# LED-Lamp-pth-v3.net
KiCad netlist of a schematic drawn in EAGLE
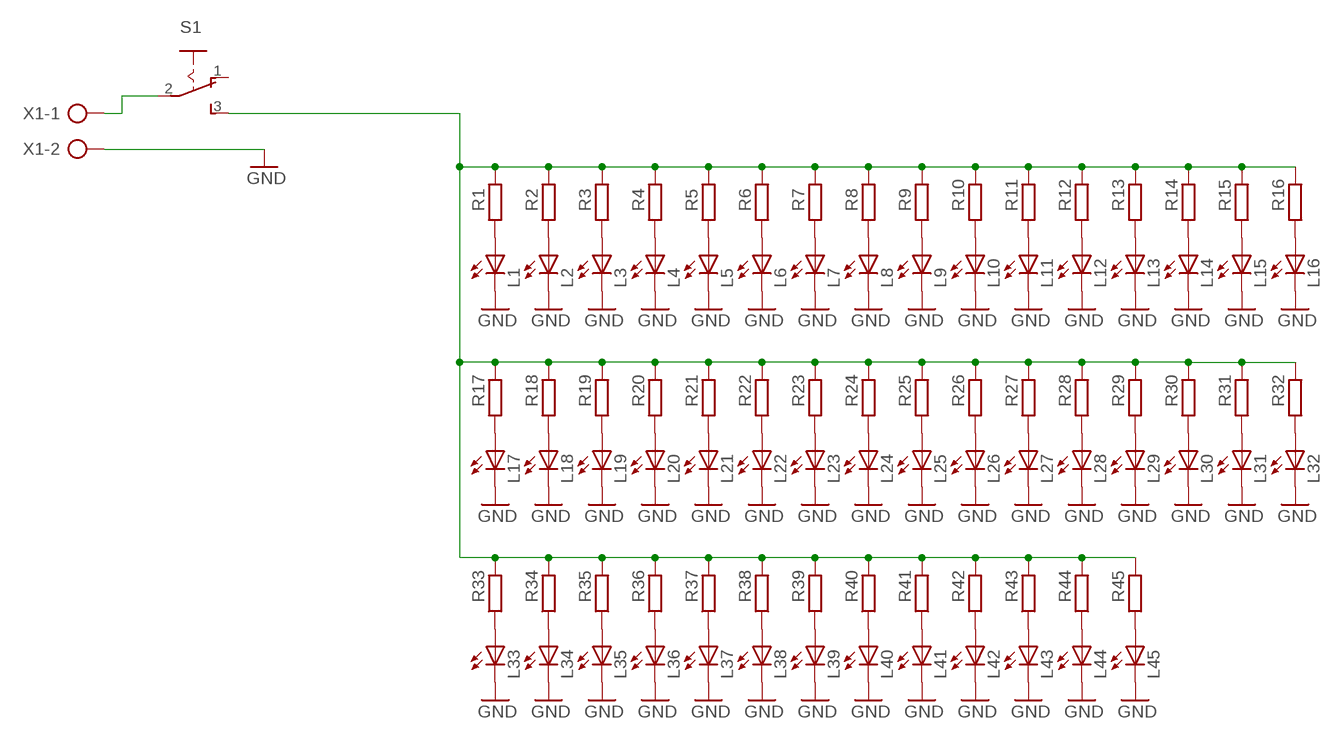
[diagram p0: schematic, sheet 1]

(export (version "E")
  (design (tool "Eeschema 10.0.6"))
  (components
    (comp (ref "L1")
      (value "LEDCHIP-LED0805")
      (footprint "eagle-import:CHIP-LED0805")
      (libsource (lib "eagle-import") (part "LEDCHIP-LED0805"))
    )
    (comp (ref "L2")
      (value "LEDCHIP-LED0805")
      (footprint "eagle-import:CHIP-LED0805")
      (libsource (lib "eagle-import") (part "LEDCHIP-LED0805"))
    )
    (comp (ref "L3")
      (value "LEDCHIP-LED0805")
      (footprint "eagle-import:CHIP-LED0805")
      (libsource (lib "eagle-import") (part "LEDCHIP-LED0805"))
    )
    (comp (ref "L4")
      (value "LEDCHIP-LED0805")
      (footprint "eagle-import:CHIP-LED0805")
      (libsource (lib "eagle-import") (part "LEDCHIP-LED0805"))
    )
    (comp (ref "L5")
      (value "LEDCHIP-LED0805")
      (footprint "eagle-import:CHIP-LED0805")
      (libsource (lib "eagle-import") (part "LEDCHIP-LED0805"))
    )
    (comp (ref "L6")
      (value "LEDCHIP-LED0805")
      (footprint "eagle-import:CHIP-LED0805")
      (libsource (lib "eagle-import") (part "LEDCHIP-LED0805"))
    )
    (comp (ref "L7")
      (value "LEDCHIP-LED0805")
      (footprint "eagle-import:CHIP-LED0805")
      (libsource (lib "eagle-import") (part "LEDCHIP-LED0805"))
    )
    (comp (ref "L8")
      (value "LEDCHIP-LED0805")
      (footprint "eagle-import:CHIP-LED0805")
      (libsource (lib "eagle-import") (part "LEDCHIP-LED0805"))
    )
    (comp (ref "L9")
      (value "LEDCHIP-LED0805")
      (footprint "eagle-import:CHIP-LED0805")
      (libsource (lib "eagle-import") (part "LEDCHIP-LED0805"))
    )
    (comp (ref "L10")
      (value "LEDCHIP-LED0805")
      (footprint "eagle-import:CHIP-LED0805")
      (libsource (lib "eagle-import") (part "LEDCHIP-LED0805"))
    )
    (comp (ref "L11")
      (value "LEDCHIP-LED0805")
      (footprint "eagle-import:CHIP-LED0805")
      (libsource (lib "eagle-import") (part "LEDCHIP-LED0805"))
    )
    (comp (ref "L12")
      (value "LEDCHIP-LED0805")
      (footprint "eagle-import:CHIP-LED0805")
      (libsource (lib "eagle-import") (part "LEDCHIP-LED0805"))
    )
    (comp (ref "L13")
      (value "LEDCHIP-LED0805")
      (footprint "eagle-import:CHIP-LED0805")
      (libsource (lib "eagle-import") (part "LEDCHIP-LED0805"))
    )
    (comp (ref "L14")
      (value "LEDCHIP-LED0805")
      (footprint "eagle-import:CHIP-LED0805")
      (libsource (lib "eagle-import") (part "LEDCHIP-LED0805"))
    )
    (comp (ref "L15")
      (value "LEDCHIP-LED0805")
      (footprint "eagle-import:CHIP-LED0805")
      (libsource (lib "eagle-import") (part "LEDCHIP-LED0805"))
    )
    (comp (ref "L16")
      (value "LEDCHIP-LED0805")
      (footprint "eagle-import:CHIP-LED0805")
      (libsource (lib "eagle-import") (part "LEDCHIP-LED0805"))
    )
    (comp (ref "L17")
      (value "LEDCHIP-LED0805")
      (footprint "eagle-import:CHIP-LED0805")
      (libsource (lib "eagle-import") (part "LEDCHIP-LED0805"))
    )
    (comp (ref "L18")
      (value "LEDCHIP-LED0805")
      (footprint "eagle-import:CHIP-LED0805")
      (libsource (lib "eagle-import") (part "LEDCHIP-LED0805"))
    )
    (comp (ref "L19")
      (value "LEDCHIP-LED0805")
      (footprint "eagle-import:CHIP-LED0805")
      (libsource (lib "eagle-import") (part "LEDCHIP-LED0805"))
    )
    (comp (ref "L20")
      (value "LEDCHIP-LED0805")
      (footprint "eagle-import:CHIP-LED0805")
      (libsource (lib "eagle-import") (part "LEDCHIP-LED0805"))
    )
    (comp (ref "L21")
      (value "LEDCHIP-LED0805")
      (footprint "eagle-import:CHIP-LED0805")
      (libsource (lib "eagle-import") (part "LEDCHIP-LED0805"))
    )
    (comp (ref "L22")
      (value "LEDCHIP-LED0805")
      (footprint "eagle-import:CHIP-LED0805")
      (libsource (lib "eagle-import") (part "LEDCHIP-LED0805"))
    )
    (comp (ref "L23")
      (value "LEDCHIP-LED0805")
      (footprint "eagle-import:CHIP-LED0805")
      (libsource (lib "eagle-import") (part "LEDCHIP-LED0805"))
    )
    (comp (ref "L24")
      (value "LEDCHIP-LED0805")
      (footprint "eagle-import:CHIP-LED0805")
      (libsource (lib "eagle-import") (part "LEDCHIP-LED0805"))
    )
    (comp (ref "L25")
      (value "LEDCHIP-LED0805")
      (footprint "eagle-import:CHIP-LED0805")
      (libsource (lib "eagle-import") (part "LEDCHIP-LED0805"))
    )
    (comp (ref "L26")
      (value "LEDCHIP-LED0805")
      (footprint "eagle-import:CHIP-LED0805")
      (libsource (lib "eagle-import") (part "LEDCHIP-LED0805"))
    )
    (comp (ref "L27")
      (value "LEDCHIP-LED0805")
      (footprint "eagle-import:CHIP-LED0805")
      (libsource (lib "eagle-import") (part "LEDCHIP-LED0805"))
    )
    (comp (ref "L28")
      (value "LEDCHIP-LED0805")
      (footprint "eagle-import:CHIP-LED0805")
      (libsource (lib "eagle-import") (part "LEDCHIP-LED0805"))
    )
    (comp (ref "L29")
      (value "LEDCHIP-LED0805")
      (footprint "eagle-import:CHIP-LED0805")
      (libsource (lib "eagle-import") (part "LEDCHIP-LED0805"))
    )
    (comp (ref "L30")
      (value "LEDCHIP-LED0805")
      (footprint "eagle-import:CHIP-LED0805")
      (libsource (lib "eagle-import") (part "LEDCHIP-LED0805"))
    )
    (comp (ref "L31")
      (value "LEDCHIP-LED0805")
      (footprint "eagle-import:CHIP-LED0805")
      (libsource (lib "eagle-import") (part "LEDCHIP-LED0805"))
    )
    (comp (ref "L32")
      (value "LEDCHIP-LED0805")
      (footprint "eagle-import:CHIP-LED0805")
      (libsource (lib "eagle-import") (part "LEDCHIP-LED0805"))
    )
    (comp (ref "L33")
      (value "LEDCHIP-LED0805")
      (footprint "eagle-import:CHIP-LED0805")
      (libsource (lib "eagle-import") (part "LEDCHIP-LED0805"))
    )
    (comp (ref "L34")
      (value "LEDCHIP-LED0805")
      (footprint "eagle-import:CHIP-LED0805")
      (libsource (lib "eagle-import") (part "LEDCHIP-LED0805"))
    )
    (comp (ref "L35")
      (value "LEDCHIP-LED0805")
      (footprint "eagle-import:CHIP-LED0805")
      (libsource (lib "eagle-import") (part "LEDCHIP-LED0805"))
    )
    (comp (ref "L36")
      (value "LEDCHIP-LED0805")
      (footprint "eagle-import:CHIP-LED0805")
      (libsource (lib "eagle-import") (part "LEDCHIP-LED0805"))
    )
    (comp (ref "L37")
      (value "LEDCHIP-LED0805")
      (footprint "eagle-import:CHIP-LED0805")
      (libsource (lib "eagle-import") (part "LEDCHIP-LED0805"))
    )
    (comp (ref "L38")
      (value "LEDCHIP-LED0805")
      (footprint "eagle-import:CHIP-LED0805")
      (libsource (lib "eagle-import") (part "LEDCHIP-LED0805"))
    )
    (comp (ref "L39")
      (value "LEDCHIP-LED0805")
      (footprint "eagle-import:CHIP-LED0805")
      (libsource (lib "eagle-import") (part "LEDCHIP-LED0805"))
    )
    (comp (ref "L40")
      (value "LEDCHIP-LED0805")
      (footprint "eagle-import:CHIP-LED0805")
      (libsource (lib "eagle-import") (part "LEDCHIP-LED0805"))
    )
    (comp (ref "L41")
      (value "LEDCHIP-LED0805")
      (footprint "eagle-import:CHIP-LED0805")
      (libsource (lib "eagle-import") (part "LEDCHIP-LED0805"))
    )
    (comp (ref "L42")
      (value "LEDCHIP-LED0805")
      (footprint "eagle-import:CHIP-LED0805")
      (libsource (lib "eagle-import") (part "LEDCHIP-LED0805"))
    )
    (comp (ref "L43")
      (value "LEDCHIP-LED0805")
      (footprint "eagle-import:CHIP-LED0805")
      (libsource (lib "eagle-import") (part "LEDCHIP-LED0805"))
    )
    (comp (ref "L44")
      (value "LEDCHIP-LED0805")
      (footprint "eagle-import:CHIP-LED0805")
      (libsource (lib "eagle-import") (part "LEDCHIP-LED0805"))
    )
    (comp (ref "L45")
      (value "LEDCHIP-LED0805")
      (footprint "eagle-import:CHIP-LED0805")
      (libsource (lib "eagle-import") (part "LEDCHIP-LED0805"))
    )
    (comp (ref "R1")
      (value "R-EU_0207/7")
      (footprint "eagle-import:0207_7")
      (libsource (lib "eagle-import") (part "R-EU_0207/7"))
    )
    (comp (ref "R2")
      (value "R-EU_0207/7")
      (footprint "eagle-import:0207_7")
      (libsource (lib "eagle-import") (part "R-EU_0207/7"))
    )
    (comp (ref "R3")
      (value "R-EU_0207/7")
      (footprint "eagle-import:0207_7")
      (libsource (lib "eagle-import") (part "R-EU_0207/7"))
    )
    (comp (ref "R4")
      (value "R-EU_0207/7")
      (footprint "eagle-import:0207_7")
      (libsource (lib "eagle-import") (part "R-EU_0207/7"))
    )
    (comp (ref "R5")
      (value "R-EU_0207/7")
      (footprint "eagle-import:0207_7")
      (libsource (lib "eagle-import") (part "R-EU_0207/7"))
    )
    (comp (ref "R6")
      (value "R-EU_0207/7")
      (footprint "eagle-import:0207_7")
      (libsource (lib "eagle-import") (part "R-EU_0207/7"))
    )
    (comp (ref "R7")
      (value "R-EU_0207/7")
      (footprint "eagle-import:0207_7")
      (libsource (lib "eagle-import") (part "R-EU_0207/7"))
    )
    (comp (ref "R8")
      (value "R-EU_0207/7")
      (footprint "eagle-import:0207_7")
      (libsource (lib "eagle-import") (part "R-EU_0207/7"))
    )
    (comp (ref "R9")
      (value "R-EU_0207/7")
      (footprint "eagle-import:0207_7")
      (libsource (lib "eagle-import") (part "R-EU_0207/7"))
    )
    (comp (ref "R10")
      (value "R-EU_0207/7")
      (footprint "eagle-import:0207_7")
      (libsource (lib "eagle-import") (part "R-EU_0207/7"))
    )
    (comp (ref "R11")
      (value "R-EU_0207/7")
      (footprint "eagle-import:0207_7")
      (libsource (lib "eagle-import") (part "R-EU_0207/7"))
    )
    (comp (ref "R12")
      (value "R-EU_0207/7")
      (footprint "eagle-import:0207_7")
      (libsource (lib "eagle-import") (part "R-EU_0207/7"))
    )
    (comp (ref "R13")
      (value "R-EU_0207/7")
      (footprint "eagle-import:0207_7")
      (libsource (lib "eagle-import") (part "R-EU_0207/7"))
    )
    (comp (ref "R14")
      (value "R-EU_0207/7")
      (footprint "eagle-import:0207_7")
      (libsource (lib "eagle-import") (part "R-EU_0207/7"))
    )
    (comp (ref "R15")
      (value "R-EU_0207/7")
      (footprint "eagle-import:0207_7")
      (libsource (lib "eagle-import") (part "R-EU_0207/7"))
    )
    (comp (ref "R16")
      (value "R-EU_0207/7")
      (footprint "eagle-import:0207_7")
      (libsource (lib "eagle-import") (part "R-EU_0207/7"))
    )
    (comp (ref "R17")
      (value "R-EU_0207/7")
      (footprint "eagle-import:0207_7")
      (libsource (lib "eagle-import") (part "R-EU_0207/7"))
    )
    (comp (ref "R18")
      (value "R-EU_0207/7")
      (footprint "eagle-import:0207_7")
      (libsource (lib "eagle-import") (part "R-EU_0207/7"))
    )
    (comp (ref "R19")
      (value "R-EU_0207/7")
      (footprint "eagle-import:0207_7")
      (libsource (lib "eagle-import") (part "R-EU_0207/7"))
    )
    (comp (ref "R20")
      (value "R-EU_0207/7")
      (footprint "eagle-import:0207_7")
      (libsource (lib "eagle-import") (part "R-EU_0207/7"))
    )
    (comp (ref "R21")
      (value "R-EU_0207/7")
      (footprint "eagle-import:0207_7")
      (libsource (lib "eagle-import") (part "R-EU_0207/7"))
    )
    (comp (ref "R22")
      (value "R-EU_0207/7")
      (footprint "eagle-import:0207_7")
      (libsource (lib "eagle-import") (part "R-EU_0207/7"))
    )
    (comp (ref "R23")
      (value "R-EU_0207/7")
      (footprint "eagle-import:0207_7")
      (libsource (lib "eagle-import") (part "R-EU_0207/7"))
    )
    (comp (ref "R24")
      (value "R-EU_0207/7")
      (footprint "eagle-import:0207_7")
      (libsource (lib "eagle-import") (part "R-EU_0207/7"))
    )
    (comp (ref "R25")
      (value "R-EU_0207/7")
      (footprint "eagle-import:0207_7")
      (libsource (lib "eagle-import") (part "R-EU_0207/7"))
    )
    (comp (ref "R26")
      (value "R-EU_0207/7")
      (footprint "eagle-import:0207_7")
      (libsource (lib "eagle-import") (part "R-EU_0207/7"))
    )
    (comp (ref "R27")
      (value "R-EU_0207/7")
      (footprint "eagle-import:0207_7")
      (libsource (lib "eagle-import") (part "R-EU_0207/7"))
    )
    (comp (ref "R28")
      (value "R-EU_0207/7")
      (footprint "eagle-import:0207_7")
      (libsource (lib "eagle-import") (part "R-EU_0207/7"))
    )
    (comp (ref "R29")
      (value "R-EU_0207/7")
      (footprint "eagle-import:0207_7")
      (libsource (lib "eagle-import") (part "R-EU_0207/7"))
    )
    (comp (ref "R30")
      (value "R-EU_0207/7")
      (footprint "eagle-import:0207_7")
      (libsource (lib "eagle-import") (part "R-EU_0207/7"))
    )
    (comp (ref "R31")
      (value "R-EU_0207/7")
      (footprint "eagle-import:0207_7")
      (libsource (lib "eagle-import") (part "R-EU_0207/7"))
    )
    (comp (ref "R32")
      (value "R-EU_0207/7")
      (footprint "eagle-import:0207_7")
      (libsource (lib "eagle-import") (part "R-EU_0207/7"))
    )
    (comp (ref "R33")
      (value "R-EU_0207/7")
      (footprint "eagle-import:0207_7")
      (libsource (lib "eagle-import") (part "R-EU_0207/7"))
    )
    (comp (ref "R34")
      (value "R-EU_0207/7")
      (footprint "eagle-import:0207_7")
      (libsource (lib "eagle-import") (part "R-EU_0207/7"))
    )
    (comp (ref "R35")
      (value "R-EU_0207/7")
      (footprint "eagle-import:0207_7")
      (libsource (lib "eagle-import") (part "R-EU_0207/7"))
    )
    (comp (ref "R36")
      (value "R-EU_0207/7")
      (footprint "eagle-import:0207_7")
      (libsource (lib "eagle-import") (part "R-EU_0207/7"))
    )
    (comp (ref "R37")
      (value "R-EU_0207/7")
      (footprint "eagle-import:0207_7")
      (libsource (lib "eagle-import") (part "R-EU_0207/7"))
    )
    (comp (ref "R38")
      (value "R-EU_0207/7")
      (footprint "eagle-import:0207_7")
      (libsource (lib "eagle-import") (part "R-EU_0207/7"))
    )
    (comp (ref "R39")
      (value "R-EU_0207/7")
      (footprint "eagle-import:0207_7")
      (libsource (lib "eagle-import") (part "R-EU_0207/7"))
    )
    (comp (ref "R40")
      (value "R-EU_0207/7")
      (footprint "eagle-import:0207_7")
      (libsource (lib "eagle-import") (part "R-EU_0207/7"))
    )
    (comp (ref "R41")
      (value "R-EU_0207/7")
      (footprint "eagle-import:0207_7")
      (libsource (lib "eagle-import") (part "R-EU_0207/7"))
    )
    (comp (ref "R42")
      (value "R-EU_0207/7")
      (footprint "eagle-import:0207_7")
      (libsource (lib "eagle-import") (part "R-EU_0207/7"))
    )
    (comp (ref "R43")
      (value "R-EU_0207/7")
      (footprint "eagle-import:0207_7")
      (libsource (lib "eagle-import") (part "R-EU_0207/7"))
    )
    (comp (ref "R44")
      (value "R-EU_0207/7")
      (footprint "eagle-import:0207_7")
      (libsource (lib "eagle-import") (part "R-EU_0207/7"))
    )
    (comp (ref "R45")
      (value "R-EU_0207/7")
      (footprint "eagle-import:0207_7")
      (libsource (lib "eagle-import") (part "R-EU_0207/7"))
    )
    (comp (ref "S1")
      (value "255SB")
      (footprint "eagle-import:255SB")
      (libsource (lib "eagle-import") (part "255SB"))
    )
    (comp (ref "X1")
      (value "AK300/2")
      (footprint "eagle-import:AK300_2")
      (libsource (lib "eagle-import") (part "AK300/2"))
    )
  )
  (nets
    (net (code "1") (name "GND") (class "Default")
      (node (ref "L1") (pin "C") (pinfunction "C_C") (pintype "passive"))
      (node (ref "L10") (pin "C") (pinfunction "C_C") (pintype "passive"))
      (node (ref "L11") (pin "C") (pinfunction "C_C") (pintype "passive"))
      (node (ref "L12") (pin "C") (pinfunction "C_C") (pintype "passive"))
      (node (ref "L13") (pin "C") (pinfunction "C_C") (pintype "passive"))
      (node (ref "L14") (pin "C") (pinfunction "C_C") (pintype "passive"))
      (node (ref "L15") (pin "C") (pinfunction "C_C") (pintype "passive"))
      (node (ref "L16") (pin "C") (pinfunction "C_C") (pintype "passive"))
      (node (ref "L17") (pin "C") (pinfunction "C_C") (pintype "passive"))
      (node (ref "L18") (pin "C") (pinfunction "C_C") (pintype "passive"))
      (node (ref "L19") (pin "C") (pinfunction "C_C") (pintype "passive"))
      (node (ref "L2") (pin "C") (pinfunction "C_C") (pintype "passive"))
      (node (ref "L20") (pin "C") (pinfunction "C_C") (pintype "passive"))
      (node (ref "L21") (pin "C") (pinfunction "C_C") (pintype "passive"))
      (node (ref "L22") (pin "C") (pinfunction "C_C") (pintype "passive"))
      (node (ref "L23") (pin "C") (pinfunction "C_C") (pintype "passive"))
      (node (ref "L24") (pin "C") (pinfunction "C_C") (pintype "passive"))
      (node (ref "L25") (pin "C") (pinfunction "C_C") (pintype "passive"))
      (node (ref "L26") (pin "C") (pinfunction "C_C") (pintype "passive"))
      (node (ref "L27") (pin "C") (pinfunction "C_C") (pintype "passive"))
      (node (ref "L28") (pin "C") (pinfunction "C_C") (pintype "passive"))
      (node (ref "L29") (pin "C") (pinfunction "C_C") (pintype "passive"))
      (node (ref "L3") (pin "C") (pinfunction "C_C") (pintype "passive"))
      (node (ref "L30") (pin "C") (pinfunction "C_C") (pintype "passive"))
      (node (ref "L31") (pin "C") (pinfunction "C_C") (pintype "passive"))
      (node (ref "L32") (pin "C") (pinfunction "C_C") (pintype "passive"))
      (node (ref "L33") (pin "C") (pinfunction "C_C") (pintype "passive"))
      (node (ref "L34") (pin "C") (pinfunction "C_C") (pintype "passive"))
      (node (ref "L35") (pin "C") (pinfunction "C_C") (pintype "passive"))
      (node (ref "L36") (pin "C") (pinfunction "C_C") (pintype "passive"))
      (node (ref "L37") (pin "C") (pinfunction "C_C") (pintype "passive"))
      (node (ref "L38") (pin "C") (pinfunction "C_C") (pintype "passive"))
      (node (ref "L39") (pin "C") (pinfunction "C_C") (pintype "passive"))
      (node (ref "L4") (pin "C") (pinfunction "C_C") (pintype "passive"))
      (node (ref "L40") (pin "C") (pinfunction "C_C") (pintype "passive"))
      (node (ref "L41") (pin "C") (pinfunction "C_C") (pintype "passive"))
      (node (ref "L42") (pin "C") (pinfunction "C_C") (pintype "passive"))
      (node (ref "L43") (pin "C") (pinfunction "C_C") (pintype "passive"))
      (node (ref "L44") (pin "C") (pinfunction "C_C") (pintype "passive"))
      (node (ref "L45") (pin "C") (pinfunction "C_C") (pintype "passive"))
      (node (ref "L5") (pin "C") (pinfunction "C_C") (pintype "passive"))
      (node (ref "L6") (pin "C") (pinfunction "C_C") (pintype "passive"))
      (node (ref "L7") (pin "C") (pinfunction "C_C") (pintype "passive"))
      (node (ref "L8") (pin "C") (pinfunction "C_C") (pintype "passive"))
      (node (ref "L9") (pin "C") (pinfunction "C_C") (pintype "passive"))
      (node (ref "X1") (pin "2") (pinfunction "KL_2") (pintype "passive"))
    )
    (net (code "2") (name "Net-(L1-PadA)") (class "Default")
      (node (ref "L1") (pin "A") (pinfunction "A_A") (pintype "passive"))
      (node (ref "R1") (pin "1") (pinfunction "1_1") (pintype "passive"))
    )
    (net (code "3") (name "Net-(L2-PadA)") (class "Default")
      (node (ref "L2") (pin "A") (pinfunction "A_A") (pintype "passive"))
      (node (ref "R2") (pin "1") (pinfunction "1_1") (pintype "passive"))
    )
    (net (code "4") (name "Net-(L3-PadA)") (class "Default")
      (node (ref "L3") (pin "A") (pinfunction "A_A") (pintype "passive"))
      (node (ref "R3") (pin "1") (pinfunction "1_1") (pintype "passive"))
    )
    (net (code "5") (name "Net-(L4-PadA)") (class "Default")
      (node (ref "L4") (pin "A") (pinfunction "A_A") (pintype "passive"))
      (node (ref "R4") (pin "1") (pinfunction "1_1") (pintype "passive"))
    )
    (net (code "6") (name "Net-(L5-PadA)") (class "Default")
      (node (ref "L5") (pin "A") (pinfunction "A_A") (pintype "passive"))
      (node (ref "R5") (pin "1") (pinfunction "1_1") (pintype "passive"))
    )
    (net (code "7") (name "Net-(L6-PadA)") (class "Default")
      (node (ref "L6") (pin "A") (pinfunction "A_A") (pintype "passive"))
      (node (ref "R6") (pin "1") (pinfunction "1_1") (pintype "passive"))
    )
    (net (code "8") (name "Net-(L7-PadA)") (class "Default")
      (node (ref "L7") (pin "A") (pinfunction "A_A") (pintype "passive"))
      (node (ref "R7") (pin "1") (pinfunction "1_1") (pintype "passive"))
    )
    (net (code "9") (name "Net-(L8-PadA)") (class "Default")
      (node (ref "L8") (pin "A") (pinfunction "A_A") (pintype "passive"))
      (node (ref "R8") (pin "1") (pinfunction "1_1") (pintype "passive"))
    )
    (net (code "10") (name "Net-(L9-PadA)") (class "Default")
      (node (ref "L9") (pin "A") (pinfunction "A_A") (pintype "passive"))
      (node (ref "R9") (pin "1") (pinfunction "1_1") (pintype "passive"))
    )
    (net (code "11") (name "Net-(L10-PadA)") (class "Default")
      (node (ref "L10") (pin "A") (pinfunction "A_A") (pintype "passive"))
      (node (ref "R10") (pin "1") (pinfunction "1_1") (pintype "passive"))
    )
    (net (code "12") (name "Net-(L11-PadA)") (class "Default")
      (node (ref "L11") (pin "A") (pinfunction "A_A") (pintype "passive"))
      (node (ref "R11") (pin "1") (pinfunction "1_1") (pintype "passive"))
    )
    (net (code "13") (name "Net-(L12-PadA)") (class "Default")
      (node (ref "L12") (pin "A") (pinfunction "A_A") (pintype "passive"))
      (node (ref "R12") (pin "1") (pinfunction "1_1") (pintype "passive"))
    )
    (net (code "14") (name "Net-(L13-PadA)") (class "Default")
      (node (ref "L13") (pin "A") (pinfunction "A_A") (pintype "passive"))
      (node (ref "R13") (pin "1") (pinfunction "1_1") (pintype "passive"))
    )
    (net (code "15") (name "Net-(L14-PadA)") (class "Default")
      (node (ref "L14") (pin "A") (pinfunction "A_A") (pintype "passive"))
      (node (ref "R14") (pin "1") (pinfunction "1_1") (pintype "passive"))
    )
    (net (code "16") (name "Net-(L15-PadA)") (class "Default")
      (node (ref "L15") (pin "A") (pinfunction "A_A") (pintype "passive"))
      (node (ref "R15") (pin "1") (pinfunction "1_1") (pintype "passive"))
    )
    (net (code "17") (name "Net-(L16-PadA)") (class "Default")
      (node (ref "L16") (pin "A") (pinfunction "A_A") (pintype "passive"))
      (node (ref "R16") (pin "1") (pinfunction "1_1") (pintype "passive"))
    )
    (net (code "18") (name "Net-(L17-PadA)") (class "Default")
      (node (ref "L17") (pin "A") (pinfunction "A_A") (pintype "passive"))
      (node (ref "R17") (pin "1") (pinfunction "1_1") (pintype "passive"))
    )
    (net (code "19") (name "Net-(L18-PadA)") (class "Default")
      (node (ref "L18") (pin "A") (pinfunction "A_A") (pintype "passive"))
      (node (ref "R18") (pin "1") (pinfunction "1_1") (pintype "passive"))
    )
    (net (code "20") (name "Net-(L19-PadA)") (class "Default")
      (node (ref "L19") (pin "A") (pinfunction "A_A") (pintype "passive"))
      (node (ref "R19") (pin "1") (pinfunction "1_1") (pintype "passive"))
    )
    (net (code "21") (name "Net-(L20-PadA)") (class "Default")
      (node (ref "L20") (pin "A") (pinfunction "A_A") (pintype "passive"))
      (node (ref "R20") (pin "1") (pinfunction "1_1") (pintype "passive"))
    )
    (net (code "22") (name "Net-(L21-PadA)") (class "Default")
      (node (ref "L21") (pin "A") (pinfunction "A_A") (pintype "passive"))
      (node (ref "R21") (pin "1") (pinfunction "1_1") (pintype "passive"))
    )
    (net (code "23") (name "Net-(L22-PadA)") (class "Default")
      (node (ref "L22") (pin "A") (pinfunction "A_A") (pintype "passive"))
      (node (ref "R22") (pin "1") (pinfunction "1_1") (pintype "passive"))
    )
    (net (code "24") (name "Net-(L23-PadA)") (class "Default")
      (node (ref "L23") (pin "A") (pinfunction "A_A") (pintype "passive"))
      (node (ref "R23") (pin "1") (pinfunction "1_1") (pintype "passive"))
    )
    (net (code "25") (name "Net-(L24-PadA)") (class "Default")
      (node (ref "L24") (pin "A") (pinfunction "A_A") (pintype "passive"))
      (node (ref "R24") (pin "1") (pinfunction "1_1") (pintype "passive"))
    )
    (net (code "26") (name "Net-(L25-PadA)") (class "Default")
      (node (ref "L25") (pin "A") (pinfunction "A_A") (pintype "passive"))
      (node (ref "R25") (pin "1") (pinfunction "1_1") (pintype "passive"))
    )
    (net (code "27") (name "Net-(L26-PadA)") (class "Default")
      (node (ref "L26") (pin "A") (pinfunction "A_A") (pintype "passive"))
      (node (ref "R26") (pin "1") (pinfunction "1_1") (pintype "passive"))
    )
    (net (code "28") (name "Net-(L27-PadA)") (class "Default")
      (node (ref "L27") (pin "A") (pinfunction "A_A") (pintype "passive"))
      (node (ref "R27") (pin "1") (pinfunction "1_1") (pintype "passive"))
    )
    (net (code "29") (name "Net-(L28-PadA)") (class "Default")
      (node (ref "L28") (pin "A") (pinfunction "A_A") (pintype "passive"))
      (node (ref "R28") (pin "1") (pinfunction "1_1") (pintype "passive"))
    )
    (net (code "30") (name "Net-(L29-PadA)") (class "Default")
      (node (ref "L29") (pin "A") (pinfunction "A_A") (pintype "passive"))
      (node (ref "R29") (pin "1") (pinfunction "1_1") (pintype "passive"))
    )
    (net (code "31") (name "Net-(L30-PadA)") (class "Default")
      (node (ref "L30") (pin "A") (pinfunction "A_A") (pintype "passive"))
      (node (ref "R30") (pin "1") (pinfunction "1_1") (pintype "passive"))
    )
    (net (code "32") (name "Net-(L31-PadA)") (class "Default")
      (node (ref "L31") (pin "A") (pinfunction "A_A") (pintype "passive"))
      (node (ref "R31") (pin "1") (pinfunction "1_1") (pintype "passive"))
    )
    (net (code "33") (name "Net-(L32-PadA)") (class "Default")
      (node (ref "L32") (pin "A") (pinfunction "A_A") (pintype "passive"))
      (node (ref "R32") (pin "1") (pinfunction "1_1") (pintype "passive"))
    )
    (net (code "34") (name "Net-(L33-PadA)") (class "Default")
      (node (ref "L33") (pin "A") (pinfunction "A_A") (pintype "passive"))
      (node (ref "R33") (pin "1") (pinfunction "1_1") (pintype "passive"))
    )
    (net (code "35") (name "Net-(L34-PadA)") (class "Default")
      (node (ref "L34") (pin "A") (pinfunction "A_A") (pintype "passive"))
      (node (ref "R34") (pin "1") (pinfunction "1_1") (pintype "passive"))
    )
    (net (code "36") (name "Net-(L35-PadA)") (class "Default")
      (node (ref "L35") (pin "A") (pinfunction "A_A") (pintype "passive"))
      (node (ref "R35") (pin "1") (pinfunction "1_1") (pintype "passive"))
    )
    (net (code "37") (name "Net-(L36-PadA)") (class "Default")
      (node (ref "L36") (pin "A") (pinfunction "A_A") (pintype "passive"))
      (node (ref "R36") (pin "1") (pinfunction "1_1") (pintype "passive"))
    )
    (net (code "38") (name "Net-(L37-PadA)") (class "Default")
      (node (ref "L37") (pin "A") (pinfunction "A_A") (pintype "passive"))
      (node (ref "R37") (pin "1") (pinfunction "1_1") (pintype "passive"))
    )
    (net (code "39") (name "Net-(L38-PadA)") (class "Default")
      (node (ref "L38") (pin "A") (pinfunction "A_A") (pintype "passive"))
      (node (ref "R38") (pin "1") (pinfunction "1_1") (pintype "passive"))
    )
    (net (code "40") (name "Net-(L39-PadA)") (class "Default")
      (node (ref "L39") (pin "A") (pinfunction "A_A") (pintype "passive"))
      (node (ref "R39") (pin "1") (pinfunction "1_1") (pintype "passive"))
    )
    (net (code "41") (name "Net-(L40-PadA)") (class "Default")
      (node (ref "L40") (pin "A") (pinfunction "A_A") (pintype "passive"))
      (node (ref "R40") (pin "1") (pinfunction "1_1") (pintype "passive"))
    )
    (net (code "42") (name "Net-(L41-PadA)") (class "Default")
      (node (ref "L41") (pin "A") (pinfunction "A_A") (pintype "passive"))
      (node (ref "R41") (pin "1") (pinfunction "1_1") (pintype "passive"))
    )
    (net (code "43") (name "Net-(L42-PadA)") (class "Default")
      (node (ref "L42") (pin "A") (pinfunction "A_A") (pintype "passive"))
      (node (ref "R42") (pin "1") (pinfunction "1_1") (pintype "passive"))
    )
    (net (code "44") (name "Net-(L43-PadA)") (class "Default")
      (node (ref "L43") (pin "A") (pinfunction "A_A") (pintype "passive"))
      (node (ref "R43") (pin "1") (pinfunction "1_1") (pintype "passive"))
    )
    (net (code "45") (name "Net-(L44-PadA)") (class "Default")
      (node (ref "L44") (pin "A") (pinfunction "A_A") (pintype "passive"))
      (node (ref "R44") (pin "1") (pinfunction "1_1") (pintype "passive"))
    )
    (net (code "46") (name "Net-(L45-PadA)") (class "Default")
      (node (ref "L45") (pin "A") (pinfunction "A_A") (pintype "passive"))
      (node (ref "R45") (pin "1") (pinfunction "1_1") (pintype "passive"))
    )
    (net (code "47") (name "Net-(S1-P)") (class "Default")
      (node (ref "S1") (pin "2") (pinfunction "P_2") (pintype "passive"))
      (node (ref "X1") (pin "1") (pinfunction "KL_1") (pintype "passive"))
    )
    (net (code "48") (name "Net-(S1-S)") (class "Default")
      (node (ref "R1") (pin "2") (pinfunction "2_2") (pintype "passive"))
      (node (ref "R10") (pin "2") (pinfunction "2_2") (pintype "passive"))
      (node (ref "R11") (pin "2") (pinfunction "2_2") (pintype "passive"))
      (node (ref "R12") (pin "2") (pinfunction "2_2") (pintype "passive"))
      (node (ref "R13") (pin "2") (pinfunction "2_2") (pintype "passive"))
      (node (ref "R14") (pin "2") (pinfunction "2_2") (pintype "passive"))
      (node (ref "R15") (pin "2") (pinfunction "2_2") (pintype "passive"))
      (node (ref "R16") (pin "2") (pinfunction "2_2") (pintype "passive"))
      (node (ref "R17") (pin "2") (pinfunction "2_2") (pintype "passive"))
      (node (ref "R18") (pin "2") (pinfunction "2_2") (pintype "passive"))
      (node (ref "R19") (pin "2") (pinfunction "2_2") (pintype "passive"))
      (node (ref "R2") (pin "2") (pinfunction "2_2") (pintype "passive"))
      (node (ref "R20") (pin "2") (pinfunction "2_2") (pintype "passive"))
      (node (ref "R21") (pin "2") (pinfunction "2_2") (pintype "passive"))
      (node (ref "R22") (pin "2") (pinfunction "2_2") (pintype "passive"))
      (node (ref "R23") (pin "2") (pinfunction "2_2") (pintype "passive"))
      (node (ref "R24") (pin "2") (pinfunction "2_2") (pintype "passive"))
      (node (ref "R25") (pin "2") (pinfunction "2_2") (pintype "passive"))
      (node (ref "R26") (pin "2") (pinfunction "2_2") (pintype "passive"))
      (node (ref "R27") (pin "2") (pinfunction "2_2") (pintype "passive"))
      (node (ref "R28") (pin "2") (pinfunction "2_2") (pintype "passive"))
      (node (ref "R29") (pin "2") (pinfunction "2_2") (pintype "passive"))
      (node (ref "R3") (pin "2") (pinfunction "2_2") (pintype "passive"))
      (node (ref "R30") (pin "2") (pinfunction "2_2") (pintype "passive"))
      (node (ref "R31") (pin "2") (pinfunction "2_2") (pintype "passive"))
      (node (ref "R32") (pin "2") (pinfunction "2_2") (pintype "passive"))
      (node (ref "R33") (pin "2") (pinfunction "2_2") (pintype "passive"))
      (node (ref "R34") (pin "2") (pinfunction "2_2") (pintype "passive"))
      (node (ref "R35") (pin "2") (pinfunction "2_2") (pintype "passive"))
      (node (ref "R36") (pin "2") (pinfunction "2_2") (pintype "passive"))
      (node (ref "R37") (pin "2") (pinfunction "2_2") (pintype "passive"))
      (node (ref "R38") (pin "2") (pinfunction "2_2") (pintype "passive"))
      (node (ref "R39") (pin "2") (pinfunction "2_2") (pintype "passive"))
      (node (ref "R4") (pin "2") (pinfunction "2_2") (pintype "passive"))
      (node (ref "R40") (pin "2") (pinfunction "2_2") (pintype "passive"))
      (node (ref "R41") (pin "2") (pinfunction "2_2") (pintype "passive"))
      (node (ref "R42") (pin "2") (pinfunction "2_2") (pintype "passive"))
      (node (ref "R43") (pin "2") (pinfunction "2_2") (pintype "passive"))
      (node (ref "R44") (pin "2") (pinfunction "2_2") (pintype "passive"))
      (node (ref "R45") (pin "2") (pinfunction "2_2") (pintype "passive"))
      (node (ref "R5") (pin "2") (pinfunction "2_2") (pintype "passive"))
      (node (ref "R6") (pin "2") (pinfunction "2_2") (pintype "passive"))
      (node (ref "R7") (pin "2") (pinfunction "2_2") (pintype "passive"))
      (node (ref "R8") (pin "2") (pinfunction "2_2") (pintype "passive"))
      (node (ref "R9") (pin "2") (pinfunction "2_2") (pintype "passive"))
      (node (ref "S1") (pin "3") (pinfunction "S_3") (pintype "passive"))
    )
    (net (code "49") (name "unconnected-(S1-O-Pad1)") (class "Default")
      (node (ref "S1") (pin "1") (pinfunction "O_1") (pintype "passive"))
    )
  )
)
